# x-OSC_Gloves_v3.net
KiCad netlist of a schematic drawn in EAGLE
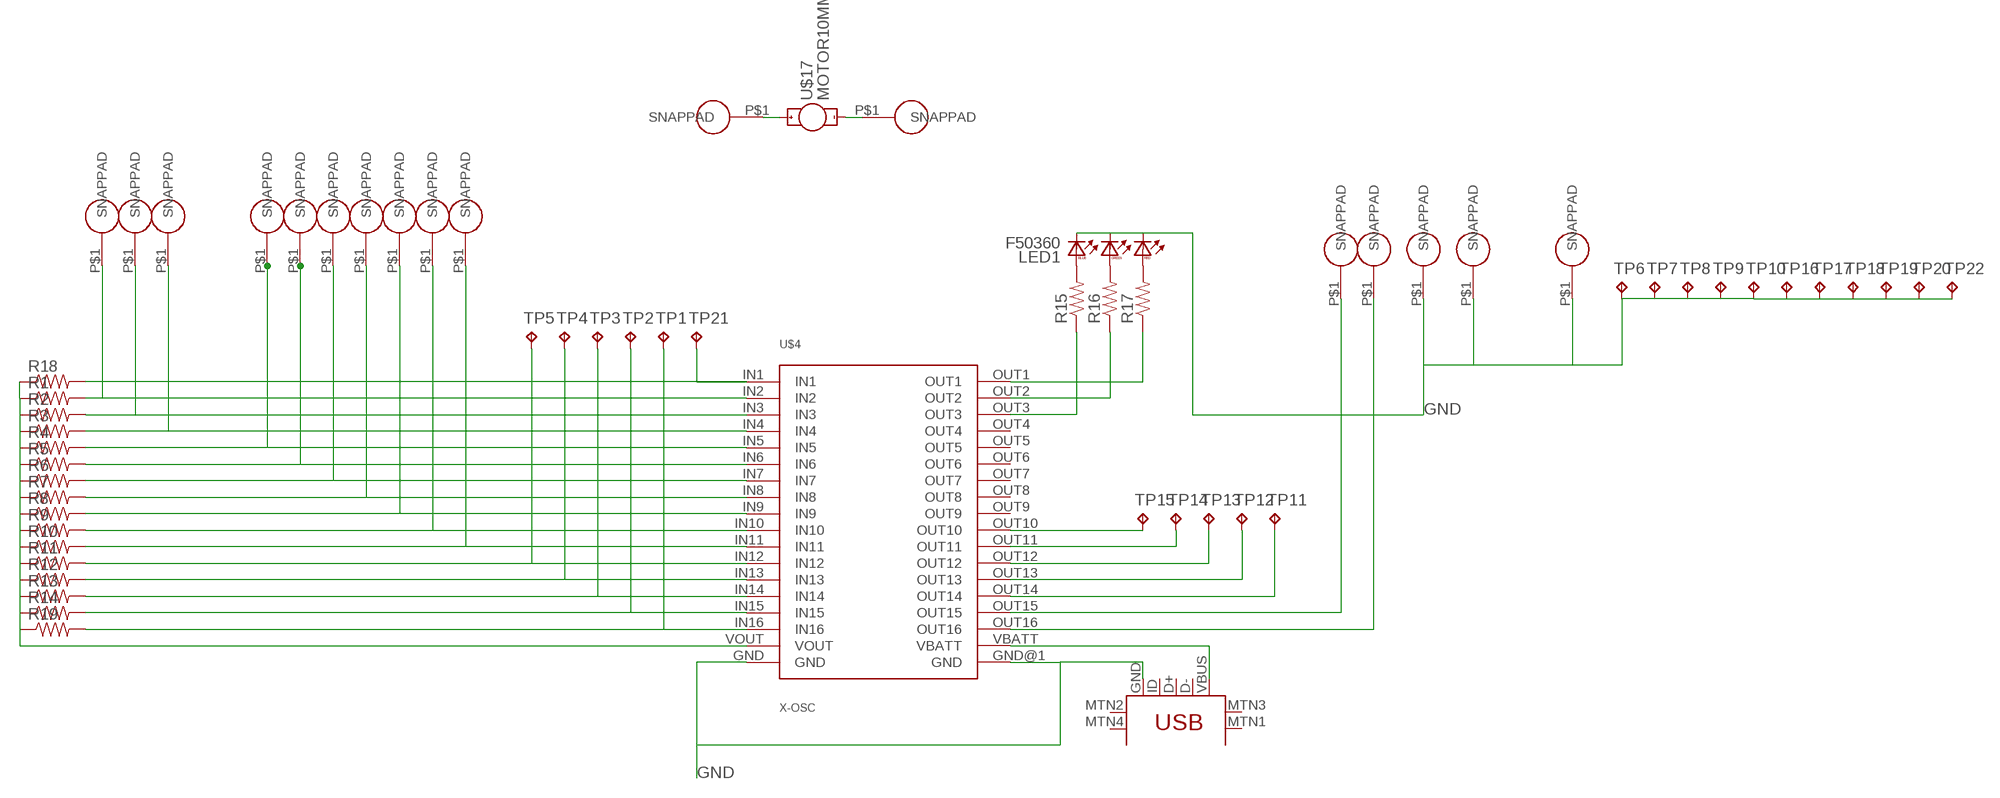
[diagram p0: schematic, sheet 1]

(export (version "E")
  (design (tool "Eeschema 10.0.6"))
  (components
    (comp (ref "LED1")
      (value "F50360")
      (footprint "eagle-import:F50360")
      (libsource (lib "eagle-import") (part "F50360"))
    )
    (comp (ref "R1")
      (value "RESISTOR0805-RES")
      (footprint "eagle-import:0805")
      (libsource (lib "eagle-import") (part "RESISTOR0805-RES"))
    )
    (comp (ref "R2")
      (value "RESISTOR0805-RES")
      (footprint "eagle-import:0805")
      (libsource (lib "eagle-import") (part "RESISTOR0805-RES"))
    )
    (comp (ref "R3")
      (value "RESISTOR0805-RES")
      (footprint "eagle-import:0805")
      (libsource (lib "eagle-import") (part "RESISTOR0805-RES"))
    )
    (comp (ref "R4")
      (value "RESISTOR0805-RES")
      (footprint "eagle-import:0805")
      (libsource (lib "eagle-import") (part "RESISTOR0805-RES"))
    )
    (comp (ref "R5")
      (value "RESISTOR0805-RES")
      (footprint "eagle-import:0805")
      (libsource (lib "eagle-import") (part "RESISTOR0805-RES"))
    )
    (comp (ref "R6")
      (value "RESISTOR0805-RES")
      (footprint "eagle-import:0805")
      (libsource (lib "eagle-import") (part "RESISTOR0805-RES"))
    )
    (comp (ref "R7")
      (value "RESISTOR0805-RES")
      (footprint "eagle-import:0805")
      (libsource (lib "eagle-import") (part "RESISTOR0805-RES"))
    )
    (comp (ref "R8")
      (value "RESISTOR0805-RES")
      (footprint "eagle-import:0805")
      (libsource (lib "eagle-import") (part "RESISTOR0805-RES"))
    )
    (comp (ref "R9")
      (value "RESISTOR0805-RES")
      (footprint "eagle-import:0805")
      (libsource (lib "eagle-import") (part "RESISTOR0805-RES"))
    )
    (comp (ref "R10")
      (value "RESISTOR0805-RES")
      (footprint "eagle-import:0805")
      (libsource (lib "eagle-import") (part "RESISTOR0805-RES"))
    )
    (comp (ref "R11")
      (value "RESISTOR0805-RES")
      (footprint "eagle-import:0805")
      (libsource (lib "eagle-import") (part "RESISTOR0805-RES"))
    )
    (comp (ref "R12")
      (value "RESISTOR0805-RES")
      (footprint "eagle-import:0805")
      (libsource (lib "eagle-import") (part "RESISTOR0805-RES"))
    )
    (comp (ref "R13")
      (value "RESISTOR0805-RES")
      (footprint "eagle-import:0805")
      (libsource (lib "eagle-import") (part "RESISTOR0805-RES"))
    )
    (comp (ref "R14")
      (value "RESISTOR0805-RES")
      (footprint "eagle-import:0805")
      (libsource (lib "eagle-import") (part "RESISTOR0805-RES"))
    )
    (comp (ref "R15")
      (value "RESISTOR0805-RES")
      (footprint "eagle-import:0805")
      (libsource (lib "eagle-import") (part "RESISTOR0805-RES"))
    )
    (comp (ref "R16")
      (value "RESISTOR0805-RES")
      (footprint "eagle-import:0805")
      (libsource (lib "eagle-import") (part "RESISTOR0805-RES"))
    )
    (comp (ref "R17")
      (value "RESISTOR0805-RES")
      (footprint "eagle-import:0805")
      (libsource (lib "eagle-import") (part "RESISTOR0805-RES"))
    )
    (comp (ref "R18")
      (value "RESISTOR0805-RES")
      (footprint "eagle-import:0805")
      (libsource (lib "eagle-import") (part "RESISTOR0805-RES"))
    )
    (comp (ref "R19")
      (value "RESISTOR0805-RES")
      (footprint "eagle-import:0805")
      (libsource (lib "eagle-import") (part "RESISTOR0805-RES"))
    )
    (comp (ref "TP1")
      (value "TPTP20R")
      (footprint "eagle-import:TP20R")
      (libsource (lib "eagle-import") (part "TPTP20R"))
    )
    (comp (ref "TP2")
      (value "TPTP20R")
      (footprint "eagle-import:TP20R")
      (libsource (lib "eagle-import") (part "TPTP20R"))
    )
    (comp (ref "TP3")
      (value "TPTP20R")
      (footprint "eagle-import:TP20R")
      (libsource (lib "eagle-import") (part "TPTP20R"))
    )
    (comp (ref "TP4")
      (value "TPTP20R")
      (footprint "eagle-import:TP20R")
      (libsource (lib "eagle-import") (part "TPTP20R"))
    )
    (comp (ref "TP5")
      (value "TPTP20R")
      (footprint "eagle-import:TP20R")
      (libsource (lib "eagle-import") (part "TPTP20R"))
    )
    (comp (ref "TP6")
      (value "TPTP20R")
      (footprint "eagle-import:TP20R")
      (libsource (lib "eagle-import") (part "TPTP20R"))
    )
    (comp (ref "TP7")
      (value "TPTP20R")
      (footprint "eagle-import:TP20R")
      (libsource (lib "eagle-import") (part "TPTP20R"))
    )
    (comp (ref "TP8")
      (value "TPTP20R")
      (footprint "eagle-import:TP20R")
      (libsource (lib "eagle-import") (part "TPTP20R"))
    )
    (comp (ref "TP9")
      (value "TPTP20R")
      (footprint "eagle-import:TP20R")
      (libsource (lib "eagle-import") (part "TPTP20R"))
    )
    (comp (ref "TP10")
      (value "TPTP20R")
      (footprint "eagle-import:TP20R")
      (libsource (lib "eagle-import") (part "TPTP20R"))
    )
    (comp (ref "TP11")
      (value "TPTP20R")
      (footprint "eagle-import:TP20R")
      (libsource (lib "eagle-import") (part "TPTP20R"))
    )
    (comp (ref "TP12")
      (value "TPTP20R")
      (footprint "eagle-import:TP20R")
      (libsource (lib "eagle-import") (part "TPTP20R"))
    )
    (comp (ref "TP13")
      (value "TPTP20R")
      (footprint "eagle-import:TP20R")
      (libsource (lib "eagle-import") (part "TPTP20R"))
    )
    (comp (ref "TP14")
      (value "TPTP20R")
      (footprint "eagle-import:TP20R")
      (libsource (lib "eagle-import") (part "TPTP20R"))
    )
    (comp (ref "TP15")
      (value "TPTP20R")
      (footprint "eagle-import:TP20R")
      (libsource (lib "eagle-import") (part "TPTP20R"))
    )
    (comp (ref "TP16")
      (value "TPTP20R")
      (footprint "eagle-import:TP20R")
      (libsource (lib "eagle-import") (part "TPTP20R"))
    )
    (comp (ref "TP17")
      (value "TPTP20R")
      (footprint "eagle-import:TP20R")
      (libsource (lib "eagle-import") (part "TPTP20R"))
    )
    (comp (ref "TP18")
      (value "TPTP20R")
      (footprint "eagle-import:TP20R")
      (libsource (lib "eagle-import") (part "TPTP20R"))
    )
    (comp (ref "TP19")
      (value "TPTP20R")
      (footprint "eagle-import:TP20R")
      (libsource (lib "eagle-import") (part "TPTP20R"))
    )
    (comp (ref "TP20")
      (value "TPTP20R")
      (footprint "eagle-import:TP20R")
      (libsource (lib "eagle-import") (part "TPTP20R"))
    )
    (comp (ref "TP21")
      (value "TPTP20R")
      (footprint "eagle-import:TP20R")
      (libsource (lib "eagle-import") (part "TPTP20R"))
    )
    (comp (ref "TP22")
      (value "TPTP20R")
      (footprint "eagle-import:TP20R")
      (libsource (lib "eagle-import") (part "TPTP20R"))
    )
    (comp (ref "U$1")
      (value "SNAP-PAD_7MM_ROUND")
      (footprint "eagle-import:SNAP-PAD_7MM_RD")
      (libsource (lib "eagle-import") (part "SNAP-PAD_7MM_ROUND"))
    )
    (comp (ref "U$2")
      (value "SNAP-PAD_7MM_ROUND")
      (footprint "eagle-import:SNAP-PAD_7MM_RD")
      (libsource (lib "eagle-import") (part "SNAP-PAD_7MM_ROUND"))
    )
    (comp (ref "U$3")
      (value "SNAP-PAD_7MM_ROUND")
      (footprint "eagle-import:SNAP-PAD_7MM_RD")
      (libsource (lib "eagle-import") (part "SNAP-PAD_7MM_ROUND"))
    )
    (comp (ref "U$4")
      (value "X-OSC")
      (footprint "eagle-import:X-OSC_SMD")
      (libsource (lib "eagle-import") (part "X-OSC"))
    )
    (comp (ref "U$5")
      (value "USB-MINIB-5PIN")
      (footprint "eagle-import:USB-MINIB")
      (libsource (lib "eagle-import") (part "USB-MINIB-5PIN"))
    )
    (comp (ref "U$6")
      (value "SNAP-PAD_7MM_ROUND")
      (footprint "eagle-import:SNAP-PAD_7MM_RD")
      (libsource (lib "eagle-import") (part "SNAP-PAD_7MM_ROUND"))
    )
    (comp (ref "U$7")
      (value "SNAP-PAD_7MM_ROUND")
      (footprint "eagle-import:SNAP-PAD_7MM_RD")
      (libsource (lib "eagle-import") (part "SNAP-PAD_7MM_ROUND"))
    )
    (comp (ref "U$8")
      (value "SNAP-PAD_7MM_ROUND")
      (footprint "eagle-import:SNAP-PAD_7MM_RD")
      (libsource (lib "eagle-import") (part "SNAP-PAD_7MM_ROUND"))
    )
    (comp (ref "U$9")
      (value "SNAP-PAD_7MM_ROUND")
      (footprint "eagle-import:SNAP-PAD_7MM_RD")
      (libsource (lib "eagle-import") (part "SNAP-PAD_7MM_ROUND"))
    )
    (comp (ref "U$10")
      (value "SNAP-PAD_7MM_ROUND")
      (footprint "eagle-import:SNAP-PAD_7MM_RD")
      (libsource (lib "eagle-import") (part "SNAP-PAD_7MM_ROUND"))
    )
    (comp (ref "U$11")
      (value "SNAP-PAD_7MM_ROUND")
      (footprint "eagle-import:SNAP-PAD_7MM_RD")
      (libsource (lib "eagle-import") (part "SNAP-PAD_7MM_ROUND"))
    )
    (comp (ref "U$12")
      (value "SNAP-PAD_7MM_ROUND")
      (footprint "eagle-import:SNAP-PAD_7MM_RD")
      (libsource (lib "eagle-import") (part "SNAP-PAD_7MM_ROUND"))
    )
    (comp (ref "U$13")
      (value "SNAP-PAD_7MM_ROUND")
      (footprint "eagle-import:SNAP-PAD_7MM_RD")
      (libsource (lib "eagle-import") (part "SNAP-PAD_7MM_ROUND"))
    )
    (comp (ref "U$14")
      (value "SNAP-PAD_7MM_ROUND")
      (footprint "eagle-import:SNAP-PAD_7MM_RD")
      (libsource (lib "eagle-import") (part "SNAP-PAD_7MM_ROUND"))
    )
    (comp (ref "U$15")
      (value "SNAP-PAD_7MM_ROUND")
      (footprint "eagle-import:SNAP-PAD_7MM_RD")
      (libsource (lib "eagle-import") (part "SNAP-PAD_7MM_ROUND"))
    )
    (comp (ref "U$16")
      (value "SNAP-PAD_7MM_ROUND")
      (footprint "eagle-import:SNAP-PAD_7MM_RD")
      (libsource (lib "eagle-import") (part "SNAP-PAD_7MM_ROUND"))
    )
    (comp (ref "U$17")
      (value "MOTOR10MM")
      (footprint "eagle-import:VIBE-MOTOR-10MM")
      (libsource (lib "eagle-import") (part "MOTOR10MM"))
    )
    (comp (ref "U$18")
      (value "SNAP-PAD_7MM_ROUND")
      (footprint "eagle-import:SNAP-PAD_7MM_RD")
      (libsource (lib "eagle-import") (part "SNAP-PAD_7MM_ROUND"))
    )
    (comp (ref "U$19")
      (value "SNAP-PAD_7MM_ROUND")
      (footprint "eagle-import:SNAP-PAD_7MM_RD")
      (libsource (lib "eagle-import") (part "SNAP-PAD_7MM_ROUND"))
    )
    (comp (ref "U$20")
      (value "SNAP-PAD_7MM_ROUND")
      (footprint "eagle-import:SNAP-PAD_7MM_RD")
      (libsource (lib "eagle-import") (part "SNAP-PAD_7MM_ROUND"))
    )
  )
  (nets
    (net (code "1") (name "/GND") (class "Default")
      (node (ref "LED1") (pin "BC") (pinfunction "BC_BC") (pintype "passive"))
      (node (ref "LED1") (pin "GC") (pinfunction "GC_GC") (pintype "passive"))
      (node (ref "LED1") (pin "RC") (pinfunction "RC_RC") (pintype "passive"))
      (node (ref "TP10") (pin "TP") (pinfunction "TP_TP") (pintype "input"))
      (node (ref "TP16") (pin "TP") (pinfunction "TP_TP") (pintype "input"))
      (node (ref "TP17") (pin "TP") (pinfunction "TP_TP") (pintype "input"))
      (node (ref "TP18") (pin "TP") (pinfunction "TP_TP") (pintype "input"))
      (node (ref "TP19") (pin "TP") (pinfunction "TP_TP") (pintype "input"))
      (node (ref "TP20") (pin "TP") (pinfunction "TP_TP") (pintype "input"))
      (node (ref "TP22") (pin "TP") (pinfunction "TP_TP") (pintype "input"))
      (node (ref "TP6") (pin "TP") (pinfunction "TP_TP") (pintype "input"))
      (node (ref "TP7") (pin "TP") (pinfunction "TP_TP") (pintype "input"))
      (node (ref "TP8") (pin "TP") (pinfunction "TP_TP") (pintype "input"))
      (node (ref "TP9") (pin "TP") (pinfunction "TP_TP") (pintype "input"))
      (node (ref "U$15") (pin "P$1") (pinfunction "SNAPPAD_P$1") (pintype "bidirectional"))
      (node (ref "U$16") (pin "P$1") (pinfunction "SNAPPAD_P$1") (pintype "bidirectional"))
      (node (ref "U$18") (pin "P$1") (pinfunction "SNAPPAD_P$1") (pintype "bidirectional"))
      (node (ref "U$4") (pin "GND") (pinfunction "GND_GND") (pintype "bidirectional"))
      (node (ref "U$4") (pin "GND@1") (pinfunction "GND_GND@1") (pintype "bidirectional"))
      (node (ref "U$5") (pin "GND") (pinfunction "GND_GND") (pintype "bidirectional"))
    )
    (net (code "2") (name "Net-(LED1-PadBA)") (class "Default")
      (node (ref "LED1") (pin "BA") (pinfunction "BA_BA") (pintype "passive"))
      (node (ref "R15") (pin "2") (pinfunction "2_2") (pintype "passive"))
    )
    (net (code "3") (name "Net-(LED1-PadGA)") (class "Default")
      (node (ref "LED1") (pin "GA") (pinfunction "GA_GA") (pintype "passive"))
      (node (ref "R16") (pin "2") (pinfunction "2_2") (pintype "passive"))
    )
    (net (code "4") (name "Net-(LED1-PadRA)") (class "Default")
      (node (ref "LED1") (pin "RA") (pinfunction "RA_RA") (pintype "passive"))
      (node (ref "R17") (pin "2") (pinfunction "2_2") (pintype "passive"))
    )
    (net (code "5") (name "Net-(R1-Pad1)") (class "Default")
      (node (ref "R1") (pin "1") (pinfunction "1_1") (pintype "passive"))
      (node (ref "R10") (pin "1") (pinfunction "1_1") (pintype "passive"))
      (node (ref "R11") (pin "1") (pinfunction "1_1") (pintype "passive"))
      (node (ref "R12") (pin "1") (pinfunction "1_1") (pintype "passive"))
      (node (ref "R13") (pin "1") (pinfunction "1_1") (pintype "passive"))
      (node (ref "R14") (pin "1") (pinfunction "1_1") (pintype "passive"))
      (node (ref "R18") (pin "1") (pinfunction "1_1") (pintype "passive"))
      (node (ref "R19") (pin "1") (pinfunction "1_1") (pintype "passive"))
      (node (ref "R2") (pin "1") (pinfunction "1_1") (pintype "passive"))
      (node (ref "R3") (pin "1") (pinfunction "1_1") (pintype "passive"))
      (node (ref "R4") (pin "1") (pinfunction "1_1") (pintype "passive"))
      (node (ref "R5") (pin "1") (pinfunction "1_1") (pintype "passive"))
      (node (ref "R6") (pin "1") (pinfunction "1_1") (pintype "passive"))
      (node (ref "R7") (pin "1") (pinfunction "1_1") (pintype "passive"))
      (node (ref "R8") (pin "1") (pinfunction "1_1") (pintype "passive"))
      (node (ref "R9") (pin "1") (pinfunction "1_1") (pintype "passive"))
      (node (ref "U$4") (pin "VOUT") (pinfunction "VOUT_VOUT") (pintype "bidirectional"))
    )
    (net (code "6") (name "Net-(R11-Pad2)") (class "Default")
      (node (ref "R11") (pin "2") (pinfunction "2_2") (pintype "passive"))
      (node (ref "TP5") (pin "TP") (pinfunction "TP_TP") (pintype "input"))
      (node (ref "U$4") (pin "IN12") (pinfunction "IN12_IN12") (pintype "bidirectional"))
    )
    (net (code "7") (name "Net-(R12-Pad2)") (class "Default")
      (node (ref "R12") (pin "2") (pinfunction "2_2") (pintype "passive"))
      (node (ref "TP4") (pin "TP") (pinfunction "TP_TP") (pintype "input"))
      (node (ref "U$4") (pin "IN13") (pinfunction "IN13_IN13") (pintype "bidirectional"))
    )
    (net (code "8") (name "Net-(R13-Pad2)") (class "Default")
      (node (ref "R13") (pin "2") (pinfunction "2_2") (pintype "passive"))
      (node (ref "TP3") (pin "TP") (pinfunction "TP_TP") (pintype "input"))
      (node (ref "U$4") (pin "IN14") (pinfunction "IN14_IN14") (pintype "bidirectional"))
    )
    (net (code "9") (name "Net-(R14-Pad2)") (class "Default")
      (node (ref "R14") (pin "2") (pinfunction "2_2") (pintype "passive"))
      (node (ref "TP2") (pin "TP") (pinfunction "TP_TP") (pintype "input"))
      (node (ref "U$4") (pin "IN15") (pinfunction "IN15_IN15") (pintype "bidirectional"))
    )
    (net (code "10") (name "Net-(R15-Pad1)") (class "Default")
      (node (ref "R15") (pin "1") (pinfunction "1_1") (pintype "passive"))
      (node (ref "U$4") (pin "OUT3") (pinfunction "OUT3_OUT3") (pintype "bidirectional"))
    )
    (net (code "11") (name "Net-(R16-Pad1)") (class "Default")
      (node (ref "R16") (pin "1") (pinfunction "1_1") (pintype "passive"))
      (node (ref "U$4") (pin "OUT2") (pinfunction "OUT2_OUT2") (pintype "bidirectional"))
    )
    (net (code "12") (name "Net-(R17-Pad1)") (class "Default")
      (node (ref "R17") (pin "1") (pinfunction "1_1") (pintype "passive"))
      (node (ref "U$4") (pin "OUT1") (pinfunction "OUT1_OUT1") (pintype "bidirectional"))
    )
    (net (code "13") (name "Net-(R18-Pad2)") (class "Default")
      (node (ref "R18") (pin "2") (pinfunction "2_2") (pintype "passive"))
      (node (ref "TP21") (pin "TP") (pinfunction "TP_TP") (pintype "input"))
      (node (ref "U$4") (pin "IN1") (pinfunction "IN1_IN1") (pintype "bidirectional"))
    )
    (net (code "14") (name "Net-(R19-Pad2)") (class "Default")
      (node (ref "R19") (pin "2") (pinfunction "2_2") (pintype "passive"))
      (node (ref "TP1") (pin "TP") (pinfunction "TP_TP") (pintype "input"))
      (node (ref "U$4") (pin "IN16") (pinfunction "IN16_IN16") (pintype "bidirectional"))
    )
    (net (code "15") (name "Net-(TP11-PadTP)") (class "Default")
      (node (ref "TP11") (pin "TP") (pinfunction "TP_TP") (pintype "input"))
      (node (ref "U$4") (pin "OUT14") (pinfunction "OUT14_OUT14") (pintype "bidirectional"))
    )
    (net (code "16") (name "Net-(TP12-PadTP)") (class "Default")
      (node (ref "TP12") (pin "TP") (pinfunction "TP_TP") (pintype "input"))
      (node (ref "U$4") (pin "OUT13") (pinfunction "OUT13_OUT13") (pintype "bidirectional"))
    )
    (net (code "17") (name "Net-(TP13-PadTP)") (class "Default")
      (node (ref "TP13") (pin "TP") (pinfunction "TP_TP") (pintype "input"))
      (node (ref "U$4") (pin "OUT12") (pinfunction "OUT12_OUT12") (pintype "bidirectional"))
    )
    (net (code "18") (name "Net-(TP14-PadTP)") (class "Default")
      (node (ref "TP14") (pin "TP") (pinfunction "TP_TP") (pintype "input"))
      (node (ref "U$4") (pin "OUT11") (pinfunction "OUT11_OUT11") (pintype "bidirectional"))
    )
    (net (code "19") (name "Net-(TP15-PadTP)") (class "Default")
      (node (ref "TP15") (pin "TP") (pinfunction "TP_TP") (pintype "input"))
      (node (ref "U$4") (pin "OUT10") (pinfunction "OUT10_OUT10") (pintype "bidirectional"))
    )
    (net (code "20") (name "Net-(U$1-SNAPPAD)") (class "Default")
      (node (ref "R1") (pin "2") (pinfunction "2_2") (pintype "passive"))
      (node (ref "U$1") (pin "P$1") (pinfunction "SNAPPAD_P$1") (pintype "bidirectional"))
      (node (ref "U$4") (pin "IN2") (pinfunction "IN2_IN2") (pintype "bidirectional"))
    )
    (net (code "21") (name "Net-(U$2-SNAPPAD)") (class "Default")
      (node (ref "R2") (pin "2") (pinfunction "2_2") (pintype "passive"))
      (node (ref "U$2") (pin "P$1") (pinfunction "SNAPPAD_P$1") (pintype "bidirectional"))
      (node (ref "U$4") (pin "IN3") (pinfunction "IN3_IN3") (pintype "bidirectional"))
    )
    (net (code "22") (name "Net-(U$3-SNAPPAD)") (class "Default")
      (node (ref "R3") (pin "2") (pinfunction "2_2") (pintype "passive"))
      (node (ref "U$3") (pin "P$1") (pinfunction "SNAPPAD_P$1") (pintype "bidirectional"))
      (node (ref "U$4") (pin "IN4") (pinfunction "IN4_IN4") (pintype "bidirectional"))
    )
    (net (code "23") (name "Net-(U$4-PadVBATT)") (class "Default")
      (node (ref "U$4") (pin "VBATT") (pinfunction "VBATT_VBATT") (pintype "bidirectional"))
      (node (ref "U$5") (pin "VBUS") (pinfunction "VBUS_VBUS") (pintype "bidirectional"))
    )
    (net (code "24") (name "Net-(U$6-SNAPPAD)") (class "Default")
      (node (ref "R4") (pin "2") (pinfunction "2_2") (pintype "passive"))
      (node (ref "U$4") (pin "IN5") (pinfunction "IN5_IN5") (pintype "bidirectional"))
      (node (ref "U$6") (pin "P$1") (pinfunction "SNAPPAD_P$1") (pintype "bidirectional"))
    )
    (net (code "25") (name "Net-(U$7-SNAPPAD)") (class "Default")
      (node (ref "R5") (pin "2") (pinfunction "2_2") (pintype "passive"))
      (node (ref "U$4") (pin "IN6") (pinfunction "IN6_IN6") (pintype "bidirectional"))
      (node (ref "U$7") (pin "P$1") (pinfunction "SNAPPAD_P$1") (pintype "bidirectional"))
    )
    (net (code "26") (name "Net-(U$8-SNAPPAD)") (class "Default")
      (node (ref "R6") (pin "2") (pinfunction "2_2") (pintype "passive"))
      (node (ref "U$4") (pin "IN7") (pinfunction "IN7_IN7") (pintype "bidirectional"))
      (node (ref "U$8") (pin "P$1") (pinfunction "SNAPPAD_P$1") (pintype "bidirectional"))
    )
    (net (code "27") (name "Net-(U$9-SNAPPAD)") (class "Default")
      (node (ref "R7") (pin "2") (pinfunction "2_2") (pintype "passive"))
      (node (ref "U$4") (pin "IN8") (pinfunction "IN8_IN8") (pintype "bidirectional"))
      (node (ref "U$9") (pin "P$1") (pinfunction "SNAPPAD_P$1") (pintype "bidirectional"))
    )
    (net (code "28") (name "Net-(U$10-SNAPPAD)") (class "Default")
      (node (ref "R8") (pin "2") (pinfunction "2_2") (pintype "passive"))
      (node (ref "U$10") (pin "P$1") (pinfunction "SNAPPAD_P$1") (pintype "bidirectional"))
      (node (ref "U$4") (pin "IN9") (pinfunction "IN9_IN9") (pintype "bidirectional"))
    )
    (net (code "29") (name "Net-(U$11-SNAPPAD)") (class "Default")
      (node (ref "R9") (pin "2") (pinfunction "2_2") (pintype "passive"))
      (node (ref "U$11") (pin "P$1") (pinfunction "SNAPPAD_P$1") (pintype "bidirectional"))
      (node (ref "U$4") (pin "IN10") (pinfunction "IN10_IN10") (pintype "bidirectional"))
    )
    (net (code "30") (name "Net-(U$12-SNAPPAD)") (class "Default")
      (node (ref "R10") (pin "2") (pinfunction "2_2") (pintype "passive"))
      (node (ref "U$12") (pin "P$1") (pinfunction "SNAPPAD_P$1") (pintype "bidirectional"))
      (node (ref "U$4") (pin "IN11") (pinfunction "IN11_IN11") (pintype "bidirectional"))
    )
    (net (code "31") (name "Net-(U$13-SNAPPAD)") (class "Default")
      (node (ref "U$13") (pin "P$1") (pinfunction "SNAPPAD_P$1") (pintype "bidirectional"))
      (node (ref "U$4") (pin "OUT15") (pinfunction "OUT15_OUT15") (pintype "bidirectional"))
    )
    (net (code "32") (name "Net-(U$14-SNAPPAD)") (class "Default")
      (node (ref "U$14") (pin "P$1") (pinfunction "SNAPPAD_P$1") (pintype "bidirectional"))
      (node (ref "U$4") (pin "OUT16") (pinfunction "OUT16_OUT16") (pintype "bidirectional"))
    )
    (net (code "33") (name "Net-(U$19-SNAPPAD)") (class "Default")
      (node (ref "U$17") (pin "+") (pinfunction "+_+") (pintype "bidirectional"))
      (node (ref "U$19") (pin "P$1") (pinfunction "SNAPPAD_P$1") (pintype "bidirectional"))
    )
    (net (code "34") (name "Net-(U$20-SNAPPAD)") (class "Default")
      (node (ref "U$17") (pin "-") (pinfunction "-_-") (pintype "bidirectional"))
      (node (ref "U$20") (pin "P$1") (pinfunction "SNAPPAD_P$1") (pintype "bidirectional"))
    )
    (net (code "35") (name "unconnected-(U$4-PadOUT4)") (class "Default")
      (node (ref "U$4") (pin "OUT4") (pinfunction "OUT4_OUT4") (pintype "bidirectional"))
    )
    (net (code "36") (name "unconnected-(U$4-PadOUT5)") (class "Default")
      (node (ref "U$4") (pin "OUT5") (pinfunction "OUT5_OUT5") (pintype "bidirectional"))
    )
    (net (code "37") (name "unconnected-(U$4-PadOUT6)") (class "Default")
      (node (ref "U$4") (pin "OUT6") (pinfunction "OUT6_OUT6") (pintype "bidirectional"))
    )
    (net (code "38") (name "unconnected-(U$4-PadOUT7)") (class "Default")
      (node (ref "U$4") (pin "OUT7") (pinfunction "OUT7_OUT7") (pintype "bidirectional"))
    )
    (net (code "39") (name "unconnected-(U$4-PadOUT8)") (class "Default")
      (node (ref "U$4") (pin "OUT8") (pinfunction "OUT8_OUT8") (pintype "bidirectional"))
    )
    (net (code "40") (name "unconnected-(U$4-PadOUT9)") (class "Default")
      (node (ref "U$4") (pin "OUT9") (pinfunction "OUT9_OUT9") (pintype "bidirectional"))
    )
    (net (code "41") (name "unconnected-(U$5-MTN1-PadMTN3)") (class "Default")
      (node (ref "U$5") (pin "MTN3") (pinfunction "MTN1_MTN3") (pintype "bidirectional"))
    )
    (net (code "42") (name "unconnected-(U$5-MTN2-PadMTN1)") (class "Default")
      (node (ref "U$5") (pin "MTN1") (pinfunction "MTN2_MTN1") (pintype "bidirectional"))
    )
    (net (code "43") (name "unconnected-(U$5-MTN3-PadMTN2)") (class "Default")
      (node (ref "U$5") (pin "MTN2") (pinfunction "MTN3_MTN2") (pintype "bidirectional"))
    )
    (net (code "44") (name "unconnected-(U$5-PadD+)") (class "Default")
      (node (ref "U$5") (pin "D+") (pinfunction "D+_D+") (pintype "bidirectional"))
    )
    (net (code "45") (name "unconnected-(U$5-PadD-)") (class "Default")
      (node (ref "U$5") (pin "D-") (pinfunction "D-_D-") (pintype "bidirectional"))
    )
    (net (code "46") (name "unconnected-(U$5-PadID)") (class "Default")
      (node (ref "U$5") (pin "ID") (pinfunction "ID_ID") (pintype "bidirectional"))
    )
    (net (code "47") (name "unconnected-(U$5-PadMTN4)") (class "Default")
      (node (ref "U$5") (pin "MTN4") (pinfunction "MTN4_MTN4") (pintype "bidirectional"))
    )
  )
)
